# Top.net
KiCad netlist of a schematic drawn in Altium Designer
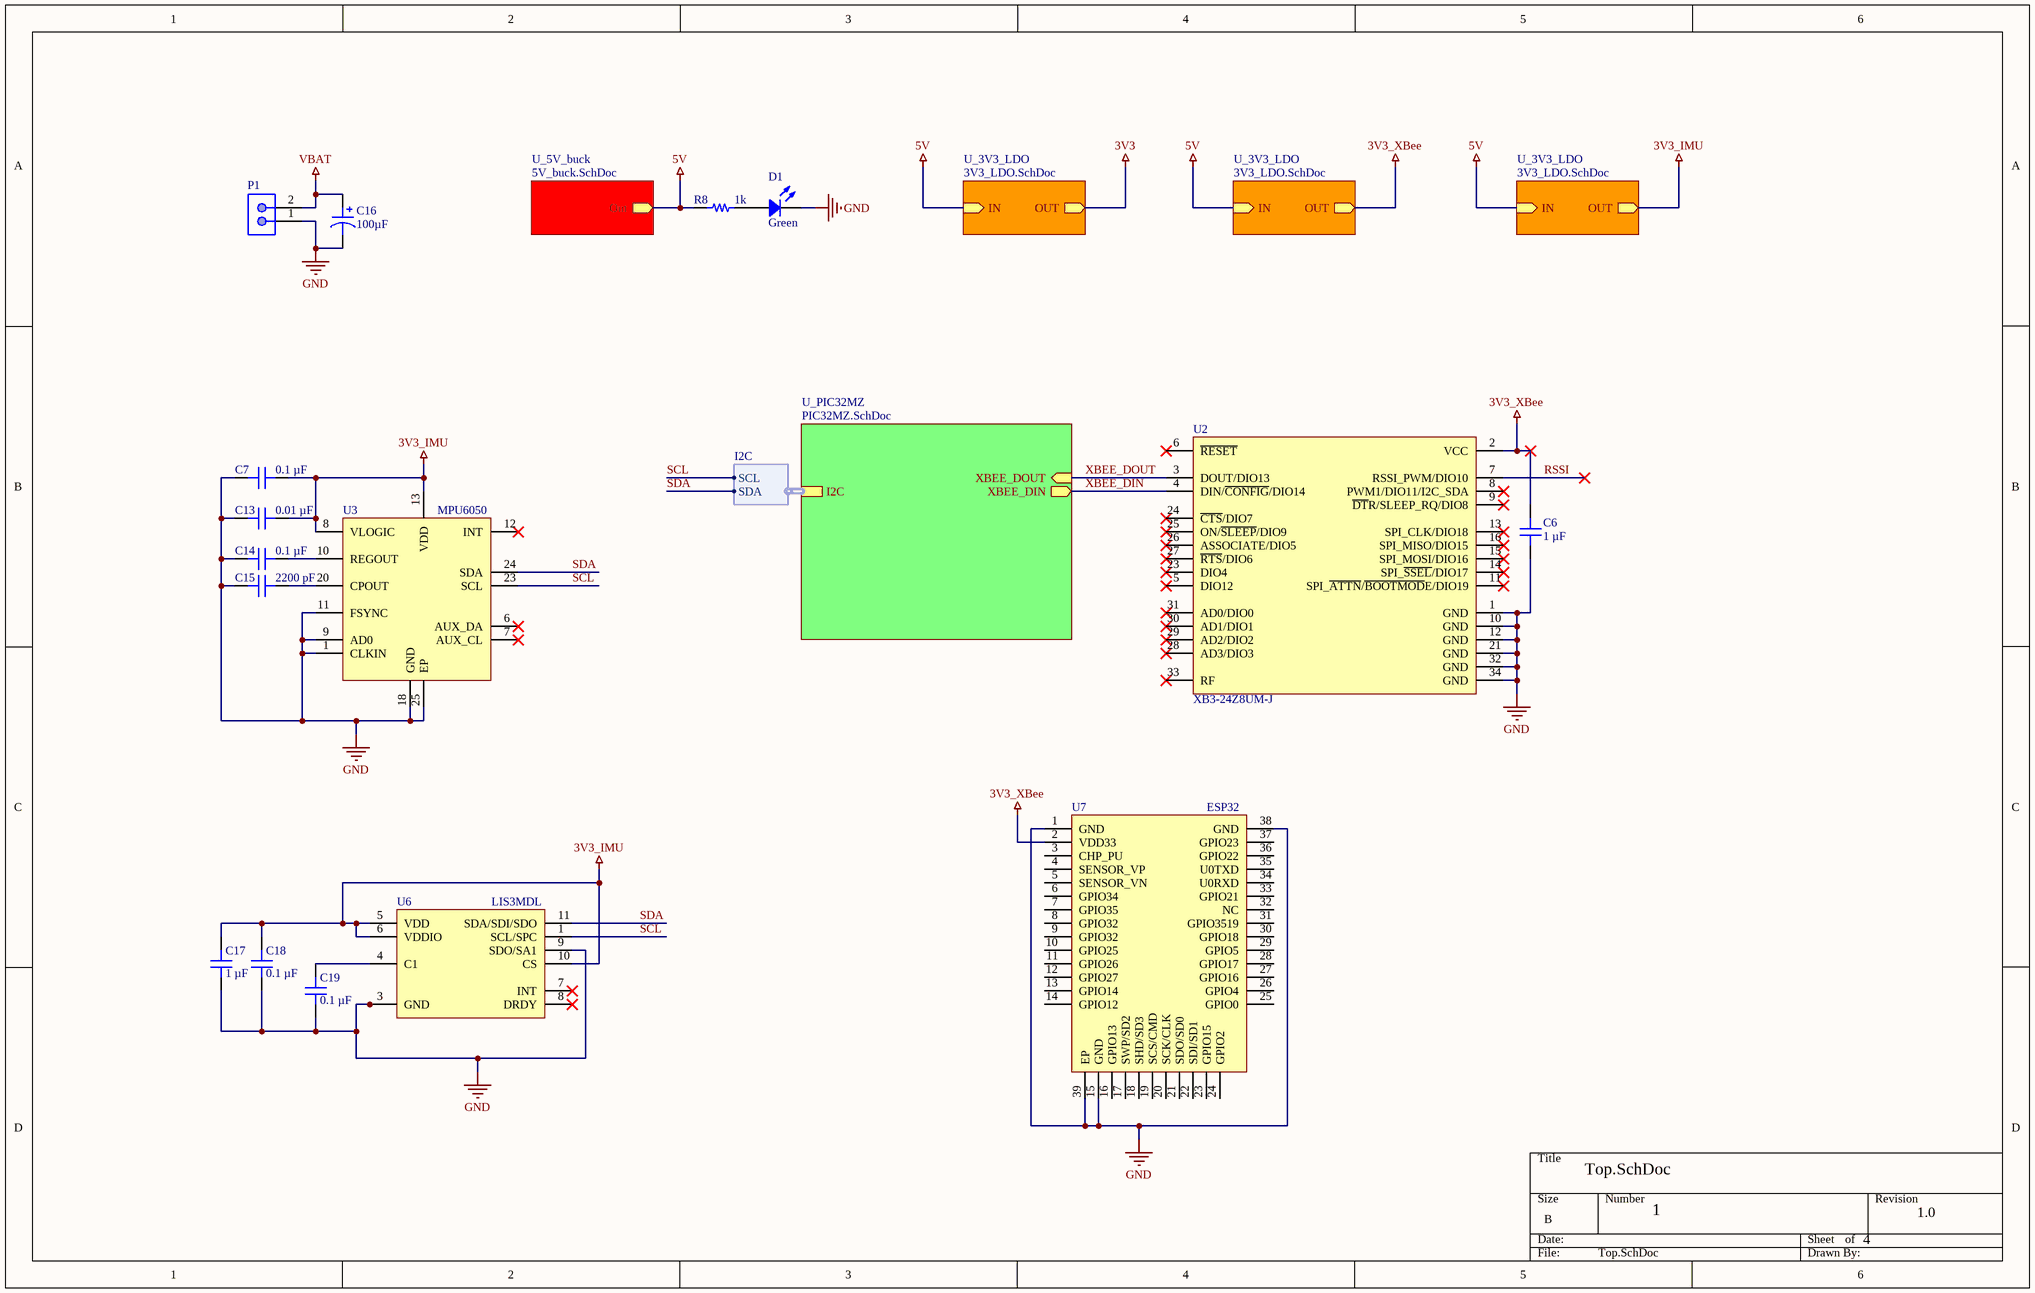
[diagram p0: Top.SchDoc]

(export (version "E")
  (design (tool "Eeschema 10.0.6"))
  (components
    (comp (ref "C6")
      (value "1 µF")
      (footprint "CAP 0402_1005")
      (description "CAP CER 0.1UF 16V X7R 0402")
      (fields (field (name "PART NUMBER") "C0402C104K4RACAUTO") (field (name "MANUFACTURER") "KEMET"))
      (libsource (lib "Celestial Altium Library - altium_library") (part "Capacitor"))
    )
    (comp (ref "C7")
      (value "0.1 µF")
      (footprint "CAP 0402_1005")
      (description "CAP CER 0.1UF 16V X7R 0402")
      (fields (field (name "PART NUMBER") "C0402C104K4RACAUTO") (field (name "MANUFACTURER") "KEMET"))
      (libsource (lib "Celestial Altium Library - altium_library") (part "Capacitor"))
    )
    (comp (ref "C13")
      (value "0.01 µF")
      (footprint "CAP 0402_1005")
      (description "CAP CER 0.1UF 16V X7R 0402")
      (fields (field (name "PART NUMBER") "C0402C104K4RACAUTO") (field (name "MANUFACTURER") "KEMET"))
      (libsource (lib "Celestial Altium Library - altium_library") (part "Capacitor"))
    )
    (comp (ref "C14")
      (value "0.1 µF")
      (footprint "CAP 0402_1005")
      (description "CAP CER 0.1UF 16V X7R 0402")
      (fields (field (name "PART NUMBER") "C0402C104K4RACAUTO") (field (name "MANUFACTURER") "KEMET"))
      (libsource (lib "Celestial Altium Library - altium_library") (part "Capacitor"))
    )
    (comp (ref "C15")
      (value "2200 pF")
      (footprint "CAP 0402_1005")
      (description "CAP CER 0.1UF 16V X7R 0402")
      (fields (field (name "PART NUMBER") "C0402C104K4RACAUTO") (field (name "MANUFACTURER") "KEMET"))
      (libsource (lib "Celestial Altium Library - altium_library") (part "Capacitor"))
    )
    (comp (ref "C16")
      (value "100µF")
      (footprint "CAP POL 2917_7343")
      (description "CAP TANT 100UF 20% 20V 2917")
      (fields (field (name "PART NUMBER") "293D107X0020E2TE3") (field (name "MANUFACTURER") "Vishay Sprague"))
      (libsource (lib "Celestial Altium Library - altium_library") (part "Polarised Capacitor"))
    )
    (comp (ref "C17")
      (value "1 µF")
      (footprint "CAP 0402_1005")
      (description "CAP CER 0.1UF 16V X7R 0402")
      (fields (field (name "PART NUMBER") "C0402C104K4RACAUTO") (field (name "MANUFACTURER") "KEMET"))
      (libsource (lib "Celestial Altium Library - altium_library") (part "Capacitor"))
    )
    (comp (ref "C18")
      (value "0.1 µF")
      (footprint "CAP 0402_1005")
      (description "CAP CER 0.1UF 16V X7R 0402")
      (fields (field (name "PART NUMBER") "C0402C104K4RACAUTO") (field (name "MANUFACTURER") "KEMET"))
      (libsource (lib "Celestial Altium Library - altium_library") (part "Capacitor"))
    )
    (comp (ref "C19")
      (value "0.1 µF")
      (footprint "CAP 0402_1005")
      (description "CAP CER 0.1UF 16V X7R 0402")
      (fields (field (name "PART NUMBER") "C0402C104K4RACAUTO") (field (name "MANUFACTURER") "KEMET"))
      (libsource (lib "Celestial Altium Library - altium_library") (part "Capacitor"))
    )
    (comp (ref "D1")
      (value "Green")
      (footprint "LED 0603_1608 GREEN")
      (description "1.6X0.8MM LC GREEN PIXSOLED DOME")
      (fields (field (name "PART NUMBER") "XZCDGK53W-8VF") (field (name "MANUFACTURER") "SunLED"))
      (libsource (lib "Celestial Altium Library - altium_library") (part "LED"))
    )
    (comp (ref "P1")
      (value "2 pin 2mm JST Male")
      (footprint "2pin - 2mm JST male")
      (libsource (lib "IC") (part "2 pin 2mm JST Male"))
    )
    (comp (ref "R8")
      (value "1k")
      (footprint "RES 0402_1005")
      (description "RES 14.3K OHM 1% 1/10W 0402")
      (fields
        (field (name "PART NUMBER") "RK73H1ETTP1432F")
        (field (name "MANUFACTURER") "KOA Speer Electronics, Inc.")
      )
      (libsource (lib "Celestial Altium Library - altium_library") (part "Resistor"))
    )
    (comp (ref "U2")
      (value "XB3-24Z8UM-J")
      (footprint "IC:XCVR_XB3-24Z8UM-J")
      (description "802.15.4 Zigbee Transceiver Module 2.4GHz Antenna Not Included, U.FL Surface Mount")
      (fields (field (name "MF") "Digi International"))
      (libsource (lib "IC") (part "XB3-24Z8UM-J"))
    )
    (comp (ref "U3") (value "MPU6050") (footprint "IC_MPU6050") (libsource (lib "IC") (part "MPU6050")))
    (comp (ref "U6")
      (value "LIS3MDL")
      (footprint "LGA12_ST")
      (description "Magnetometer")
      (libsource (lib "IC") (part "LIS3MDL"))
    )
    (comp (ref "U7")
      (value "ESP32")
      (footprint "Espressif ESP32-WROOM-32")
      (libsource (lib "IC") (part "ESP32"))
    )
  )
  (nets
    (net (code "2") (name "/RSSI") (class "Default")
      (node (ref "U2") (pin "7") (pinfunction "RSSI_PWM/DIO10_7") (pintype "passive+no_connect"))
    )
    (net (code "3") (name "/SCL") (class "Default")
      (node (ref "U3") (pin "23") (pinfunction "SCL_23") (pintype "passive"))
      (node (ref "U6") (pin "1") (pinfunction "SCL/SPC_1") (pintype "passive"))
    )
    (net (code "4") (name "/SDA") (class "Default")
      (node (ref "U3") (pin "24") (pinfunction "SDA_24") (pintype "passive"))
      (node (ref "U6") (pin "11") (pinfunction "SDA/SDI/SDO_11") (pintype "passive"))
    )
    (net (code "5") (name "/XBEE_DIN") (class "Default")
      (node (ref "U2") (pin "4") (pinfunction "DIN/~{CONFIG}/DIO14_4") (pintype "passive"))
    )
    (net (code "6") (name "/XBEE_DOUT") (class "Default")
      (node (ref "U2") (pin "3") (pinfunction "DOUT/DIO13_3") (pintype "passive"))
    )
    (net (code "9") (name "3V3_IMU") (class "Default")
      (node (ref "C13") (pin "1") (pinfunction "1_1") (pintype "passive"))
      (node (ref "C17") (pin "1") (pinfunction "1_1") (pintype "passive"))
      (node (ref "C18") (pin "1") (pinfunction "1_1") (pintype "passive"))
      (node (ref "C7") (pin "1") (pinfunction "1_1") (pintype "passive"))
      (node (ref "U3") (pin "13") (pinfunction "VDD_13") (pintype "passive"))
      (node (ref "U3") (pin "8") (pinfunction "VLOGIC_8") (pintype "passive"))
      (node (ref "U6") (pin "10") (pinfunction "CS_10") (pintype "passive"))
      (node (ref "U6") (pin "5") (pinfunction "VDD_5") (pintype "passive"))
      (node (ref "U6") (pin "6") (pinfunction "VDDIO_6") (pintype "passive"))
    )
    (net (code "10") (name "3V3_XBee") (class "Default")
      (node (ref "C6") (pin "1") (pinfunction "1_1") (pintype "passive"))
      (node (ref "U2") (pin "2") (pinfunction "VCC_2") (pintype "power_in"))
      (node (ref "U7") (pin "2") (pinfunction "VDD33_2") (pintype "passive"))
    )
    (net (code "11") (name "5V") (class "Default")
      (node (ref "R8") (pin "1") (pinfunction "1_1") (pintype "passive"))
    )
    (net (code "12") (name "GND") (class "Default")
      (node (ref "C13") (pin "2") (pinfunction "2_2") (pintype "passive"))
      (node (ref "C14") (pin "2") (pinfunction "2_2") (pintype "passive"))
      (node (ref "C15") (pin "2") (pinfunction "2_2") (pintype "passive"))
      (node (ref "C16") (pin "2") (pinfunction "2_2") (pintype "passive"))
      (node (ref "C17") (pin "2") (pinfunction "2_2") (pintype "passive"))
      (node (ref "C18") (pin "2") (pinfunction "2_2") (pintype "passive"))
      (node (ref "C19") (pin "2") (pinfunction "2_2") (pintype "passive"))
      (node (ref "C6") (pin "2") (pinfunction "2_2") (pintype "passive"))
      (node (ref "C7") (pin "2") (pinfunction "2_2") (pintype "passive"))
      (node (ref "D1") (pin "2") (pinfunction "2_2") (pintype "passive"))
      (node (ref "P1") (pin "1") (pinfunction "1_1") (pintype "passive"))
      (node (ref "U2") (pin "1") (pinfunction "GND_1") (pintype "power_in"))
      (node (ref "U2") (pin "10") (pinfunction "GND_10") (pintype "power_in"))
      (node (ref "U2") (pin "12") (pinfunction "GND_12") (pintype "power_in"))
      (node (ref "U2") (pin "21") (pinfunction "GND_21") (pintype "power_in"))
      (node (ref "U2") (pin "32") (pinfunction "GND_32") (pintype "power_in"))
      (node (ref "U2") (pin "34") (pinfunction "GND_34") (pintype "power_in"))
      (node (ref "U3") (pin "1") (pinfunction "CLKIN_1") (pintype "passive"))
      (node (ref "U3") (pin "11") (pinfunction "FSYNC_11") (pintype "passive"))
      (node (ref "U3") (pin "18") (pinfunction "GND_18") (pintype "passive"))
      (node (ref "U3") (pin "25") (pinfunction "EP_25") (pintype "passive"))
      (node (ref "U3") (pin "9") (pinfunction "AD0_9") (pintype "passive"))
      (node (ref "U6") (pin "12") (pinfunction "Reserved_12") (pintype "passive"))
      (node (ref "U6") (pin "2") (pinfunction "Reserved_2") (pintype "passive"))
      (node (ref "U6") (pin "3") (pinfunction "GND_3") (pintype "passive"))
      (node (ref "U6") (pin "9") (pinfunction "SDO/SA1_9") (pintype "passive"))
      (node (ref "U7") (pin "1") (pinfunction "GND_1") (pintype "passive"))
      (node (ref "U7") (pin "15") (pinfunction "GND_15") (pintype "passive"))
      (node (ref "U7") (pin "38") (pinfunction "GND_38") (pintype "passive"))
      (node (ref "U7") (pin "39") (pinfunction "EP_39") (pintype "passive"))
    )
    (net (code "13") (name "Net-(D1-Pad1)") (class "Default")
      (node (ref "D1") (pin "1") (pinfunction "1_1") (pintype "passive"))
      (node (ref "R8") (pin "2") (pinfunction "2_2") (pintype "passive"))
    )
    (net (code "14") (name "Net-(U3-CPOUT)") (class "Default")
      (node (ref "C15") (pin "1") (pinfunction "1_1") (pintype "passive"))
      (node (ref "U3") (pin "20") (pinfunction "CPOUT_20") (pintype "passive"))
    )
    (net (code "15") (name "Net-(U3-REGOUT)") (class "Default")
      (node (ref "C14") (pin "1") (pinfunction "1_1") (pintype "passive"))
      (node (ref "U3") (pin "10") (pinfunction "REGOUT_10") (pintype "passive"))
    )
    (net (code "16") (name "Net-(U6-C1)") (class "Default")
      (node (ref "C19") (pin "1") (pinfunction "1_1") (pintype "passive"))
      (node (ref "U6") (pin "4") (pinfunction "C1_4") (pintype "passive"))
    )
    (net (code "17") (name "VBAT") (class "Default")
      (node (ref "C16") (pin "1") (pinfunction "1_1") (pintype "passive"))
      (node (ref "P1") (pin "2") (pinfunction "2_2") (pintype "passive"))
    )
    (net (code "18") (name "unconnected-(U2-AD0{slash}DIO0-Pad31)") (class "Default")
      (node (ref "U2") (pin "31") (pinfunction "AD0/DIO0_31") (pintype "passive+no_connect"))
    )
    (net (code "19") (name "unconnected-(U2-AD1{slash}DIO1-Pad30)") (class "Default")
      (node (ref "U2") (pin "30") (pinfunction "AD1/DIO1_30") (pintype "passive+no_connect"))
    )
    (net (code "20") (name "unconnected-(U2-AD2{slash}DIO2-Pad29)") (class "Default")
      (node (ref "U2") (pin "29") (pinfunction "AD2/DIO2_29") (pintype "passive+no_connect"))
    )
    (net (code "21") (name "unconnected-(U2-AD3{slash}DIO3-Pad28)") (class "Default")
      (node (ref "U2") (pin "28") (pinfunction "AD3/DIO3_28") (pintype "passive+no_connect"))
    )
    (net (code "22") (name "unconnected-(U2-ASSOCIATE{slash}DIO5-Pad26)") (class "Default")
      (node (ref "U2") (pin "26") (pinfunction "ASSOCIATE/DIO5_26") (pintype "passive+no_connect"))
    )
    (net (code "23") (name "unconnected-(U2-DIO4-Pad23)") (class "Default")
      (node (ref "U2") (pin "23") (pinfunction "DIO4_23") (pintype "passive+no_connect"))
    )
    (net (code "24") (name "unconnected-(U2-DIO12-Pad5)") (class "Default")
      (node (ref "U2") (pin "5") (pinfunction "DIO12_5") (pintype "passive+no_connect"))
    )
    (net (code "25") (name "unconnected-(U2-ON{slash}~{SLEEP}{slash}DIO9-Pad25)") (class "Default")
      (node (ref "U2") (pin "25") (pinfunction "ON/~{SLEEP}/DIO9_25") (pintype "passive+no_connect"))
    )
    (net (code "26") (name "unconnected-(U2-PWM1{slash}DIO11{slash}I2C_SDA-Pad8)") (class "Default")
      (node (ref "U2") (pin "8") (pinfunction "PWM1/DIO11/I2C_SDA_8") (pintype "passive+no_connect"))
    )
    (net (code "27") (name "unconnected-(U2-RF-Pad33)") (class "Default")
      (node (ref "U2") (pin "33") (pinfunction "RF_33") (pintype "passive+no_connect"))
    )
    (net (code "28") (name "unconnected-(U2-SPI_CLK{slash}DIO18-Pad13)") (class "Default")
      (node (ref "U2") (pin "13") (pinfunction "SPI_CLK/DIO18_13") (pintype "passive+no_connect"))
    )
    (net (code "29") (name "unconnected-(U2-SPI_MISO{slash}DIO15-Pad16)") (class "Default")
      (node (ref "U2") (pin "16") (pinfunction "SPI_MISO/DIO15_16") (pintype "passive+no_connect"))
    )
    (net (code "30") (name "unconnected-(U2-SPI_MOSI{slash}DIO16-Pad15)") (class "Default")
      (node (ref "U2") (pin "15") (pinfunction "SPI_MOSI/DIO16_15") (pintype "passive+no_connect"))
    )
    (net (code "31") (name "unconnected-(U2-SPI_~{ATTN}{slash}~{BOOTMOD}E{slash}DIO19-Pad11)") (class "Default")
      (node (ref "U2") (pin "11") (pinfunction "SPI_~{ATTN}/~{BOOTMOD}E/DIO19_11") (pintype "passive+no_connect"))
    )
    (net (code "32") (name "unconnected-(U2-SPI_~{SSEL}{slash}DIO17-Pad14)") (class "Default")
      (node (ref "U2") (pin "14") (pinfunction "SPI_~{SSEL}/DIO17_14") (pintype "passive+no_connect"))
    )
    (net (code "33") (name "unconnected-(U2-~{CTS}{slash}DIO7-Pad24)") (class "Default")
      (node (ref "U2") (pin "24") (pinfunction "~{CTS}/DIO7_24") (pintype "passive+no_connect"))
    )
    (net (code "34") (name "unconnected-(U2-~{DT}R{slash}SLEEP_RQ{slash}DIO8-Pad9)") (class "Default")
      (node (ref "U2") (pin "9") (pinfunction "~{DT}R/SLEEP_RQ/DIO8_9") (pintype "passive+no_connect"))
    )
    (net (code "35") (name "unconnected-(U2-~{RESET}-Pad6)") (class "Default")
      (node (ref "U2") (pin "6") (pinfunction "~{RESET}_6") (pintype "passive+no_connect"))
    )
    (net (code "36") (name "unconnected-(U2-~{RTS}{slash}DIO6-Pad27)") (class "Default")
      (node (ref "U2") (pin "27") (pinfunction "~{RTS}/DIO6_27") (pintype "passive+no_connect"))
    )
    (net (code "37") (name "unconnected-(U3-AUX_CL-Pad7)") (class "Default")
      (node (ref "U3") (pin "7") (pinfunction "AUX_CL_7") (pintype "passive+no_connect"))
    )
    (net (code "38") (name "unconnected-(U3-AUX_DA-Pad6)") (class "Default")
      (node (ref "U3") (pin "6") (pinfunction "AUX_DA_6") (pintype "passive+no_connect"))
    )
    (net (code "39") (name "unconnected-(U3-INT-Pad12)") (class "Default")
      (node (ref "U3") (pin "12") (pinfunction "INT_12") (pintype "passive+no_connect"))
    )
    (net (code "40") (name "unconnected-(U6-DRDY-Pad8)") (class "Default")
      (node (ref "U6") (pin "8") (pinfunction "DRDY_8") (pintype "passive+no_connect"))
    )
    (net (code "41") (name "unconnected-(U6-INT-Pad7)") (class "Default")
      (node (ref "U6") (pin "7") (pinfunction "INT_7") (pintype "passive+no_connect"))
    )
    (net (code "42") (name "unconnected-(U7-CHP_PU-Pad3)") (class "Default")
      (node (ref "U7") (pin "3") (pinfunction "CHP_PU_3") (pintype "passive"))
    )
    (net (code "43") (name "unconnected-(U7-GPIO0-Pad25)") (class "Default")
      (node (ref "U7") (pin "25") (pinfunction "GPIO0_25") (pintype "passive"))
    )
    (net (code "44") (name "unconnected-(U7-GPIO2-Pad24)") (class "Default")
      (node (ref "U7") (pin "24") (pinfunction "GPIO2_24") (pintype "passive"))
    )
    (net (code "45") (name "unconnected-(U7-GPIO4-Pad26)") (class "Default")
      (node (ref "U7") (pin "26") (pinfunction "GPIO4_26") (pintype "passive"))
    )
    (net (code "46") (name "unconnected-(U7-GPIO5-Pad29)") (class "Default")
      (node (ref "U7") (pin "29") (pinfunction "GPIO5_29") (pintype "passive"))
    )
    (net (code "47") (name "unconnected-(U7-GPIO12-Pad14)") (class "Default")
      (node (ref "U7") (pin "14") (pinfunction "GPIO12_14") (pintype "passive"))
    )
    (net (code "48") (name "unconnected-(U7-GPIO13-Pad16)") (class "Default")
      (node (ref "U7") (pin "16") (pinfunction "GPIO13_16") (pintype "passive"))
    )
    (net (code "49") (name "unconnected-(U7-GPIO14-Pad13)") (class "Default")
      (node (ref "U7") (pin "13") (pinfunction "GPIO14_13") (pintype "passive"))
    )
    (net (code "50") (name "unconnected-(U7-GPIO15-Pad23)") (class "Default")
      (node (ref "U7") (pin "23") (pinfunction "GPIO15_23") (pintype "passive"))
    )
    (net (code "51") (name "unconnected-(U7-GPIO16-Pad27)") (class "Default")
      (node (ref "U7") (pin "27") (pinfunction "GPIO16_27") (pintype "passive"))
    )
    (net (code "52") (name "unconnected-(U7-GPIO17-Pad28)") (class "Default")
      (node (ref "U7") (pin "28") (pinfunction "GPIO17_28") (pintype "passive"))
    )
    (net (code "53") (name "unconnected-(U7-GPIO18-Pad30)") (class "Default")
      (node (ref "U7") (pin "30") (pinfunction "GPIO18_30") (pintype "passive"))
    )
    (net (code "54") (name "unconnected-(U7-GPIO21-Pad33)") (class "Default")
      (node (ref "U7") (pin "33") (pinfunction "GPIO21_33") (pintype "passive"))
    )
    (net (code "55") (name "unconnected-(U7-GPIO22-Pad36)") (class "Default")
      (node (ref "U7") (pin "36") (pinfunction "GPIO22_36") (pintype "passive"))
    )
    (net (code "56") (name "unconnected-(U7-GPIO23-Pad37)") (class "Default")
      (node (ref "U7") (pin "37") (pinfunction "GPIO23_37") (pintype "passive"))
    )
    (net (code "57") (name "unconnected-(U7-GPIO25-Pad10)") (class "Default")
      (node (ref "U7") (pin "10") (pinfunction "GPIO25_10") (pintype "passive"))
    )
    (net (code "58") (name "unconnected-(U7-GPIO26-Pad11)") (class "Default")
      (node (ref "U7") (pin "11") (pinfunction "GPIO26_11") (pintype "passive"))
    )
    (net (code "59") (name "unconnected-(U7-GPIO27-Pad12)") (class "Default")
      (node (ref "U7") (pin "12") (pinfunction "GPIO27_12") (pintype "passive"))
    )
    (net (code "60") (name "unconnected-(U7-GPIO32-Pad8)") (class "Default")
      (node (ref "U7") (pin "8") (pinfunction "GPIO32_8") (pintype "passive"))
    )
    (net (code "61") (name "unconnected-(U7-GPIO32-Pad9)") (class "Default")
      (node (ref "U7") (pin "9") (pinfunction "GPIO32_9") (pintype "passive"))
    )
    (net (code "62") (name "unconnected-(U7-GPIO34-Pad6)") (class "Default")
      (node (ref "U7") (pin "6") (pinfunction "GPIO34_6") (pintype "passive"))
    )
    (net (code "63") (name "unconnected-(U7-GPIO35-Pad7)") (class "Default")
      (node (ref "U7") (pin "7") (pinfunction "GPIO35_7") (pintype "passive"))
    )
    (net (code "64") (name "unconnected-(U7-GPIO3519-Pad31)") (class "Default")
      (node (ref "U7") (pin "31") (pinfunction "GPIO3519_31") (pintype "passive"))
    )
    (net (code "65") (name "unconnected-(U7-NC-Pad32)") (class "Default")
      (node (ref "U7") (pin "32") (pinfunction "NC_32") (pintype "passive"))
    )
    (net (code "66") (name "unconnected-(U7-SCK{slash}CLK-Pad20)") (class "Default")
      (node (ref "U7") (pin "20") (pinfunction "SCK/CLK_20") (pintype "passive"))
    )
    (net (code "67") (name "unconnected-(U7-SCS{slash}CMD-Pad19)") (class "Default")
      (node (ref "U7") (pin "19") (pinfunction "SCS/CMD_19") (pintype "passive"))
    )
    (net (code "68") (name "unconnected-(U7-SDI{slash}SD1-Pad22)") (class "Default")
      (node (ref "U7") (pin "22") (pinfunction "SDI/SD1_22") (pintype "passive"))
    )
    (net (code "69") (name "unconnected-(U7-SDO{slash}SD0-Pad21)") (class "Default")
      (node (ref "U7") (pin "21") (pinfunction "SDO/SD0_21") (pintype "passive"))
    )
    (net (code "70") (name "unconnected-(U7-SENSOR_VN-Pad5)") (class "Default")
      (node (ref "U7") (pin "5") (pinfunction "SENSOR_VN_5") (pintype "passive"))
    )
    (net (code "71") (name "unconnected-(U7-SENSOR_VP-Pad4)") (class "Default")
      (node (ref "U7") (pin "4") (pinfunction "SENSOR_VP_4") (pintype "passive"))
    )
    (net (code "72") (name "unconnected-(U7-SHD{slash}SD3-Pad18)") (class "Default")
      (node (ref "U7") (pin "18") (pinfunction "SHD/SD3_18") (pintype "passive"))
    )
    (net (code "73") (name "unconnected-(U7-SWP{slash}SD2-Pad17)") (class "Default")
      (node (ref "U7") (pin "17") (pinfunction "SWP/SD2_17") (pintype "passive"))
    )
    (net (code "74") (name "unconnected-(U7-U0RXD-Pad34)") (class "Default")
      (node (ref "U7") (pin "34") (pinfunction "U0RXD_34") (pintype "passive"))
    )
    (net (code "75") (name "unconnected-(U7-U0TXD-Pad35)") (class "Default")
      (node (ref "U7") (pin "35") (pinfunction "U0TXD_35") (pintype "passive"))
    )
  )
)
